# Tiny_Tetris_v1_3.net
KiCad netlist of a schematic drawn in EAGLE
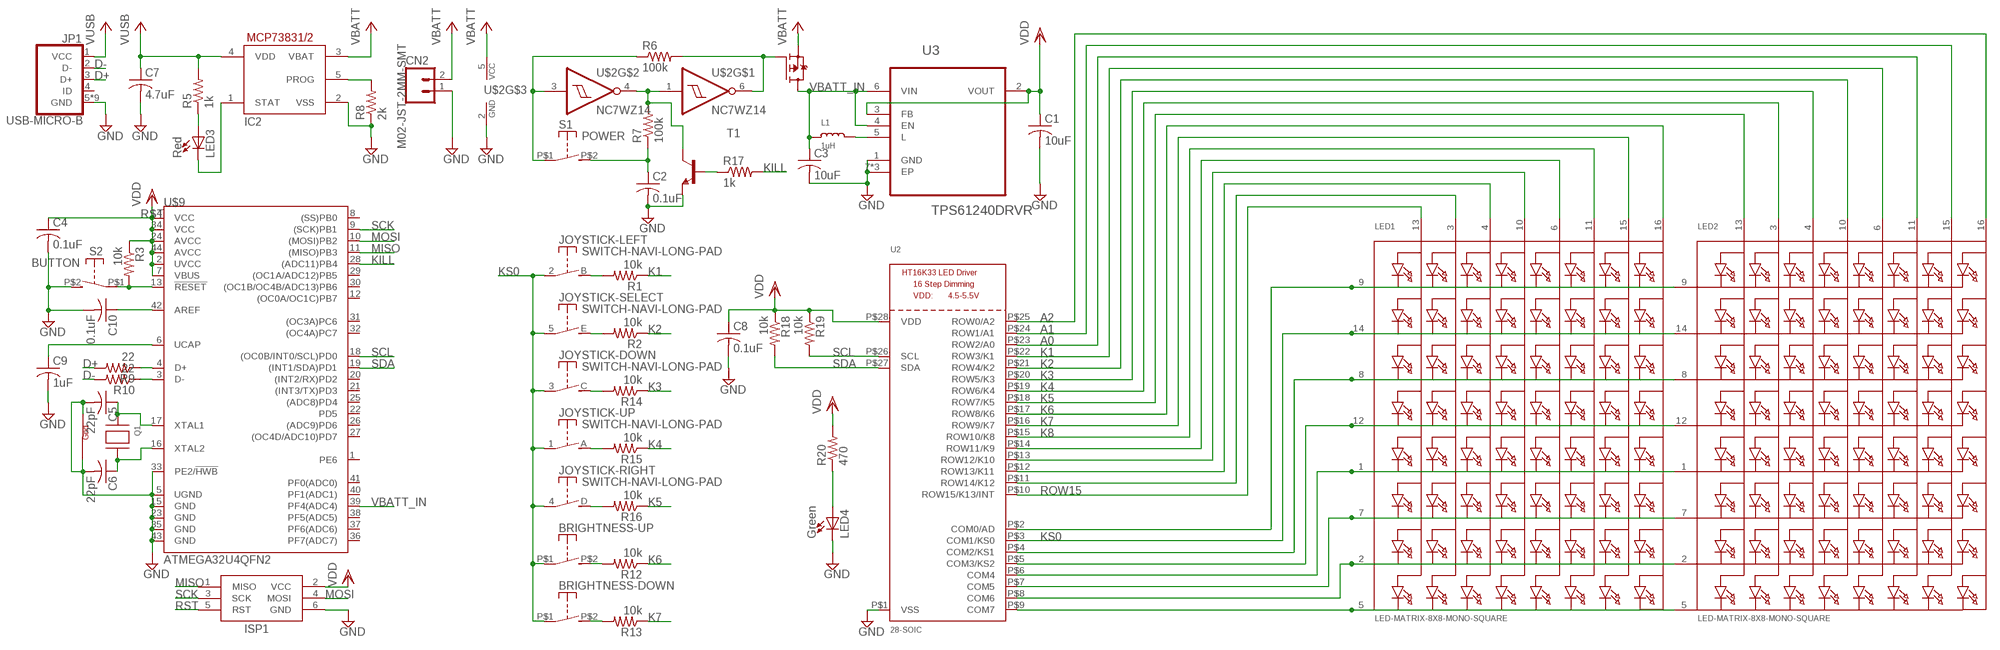
[diagram p0: schematic, sheet 1]

(export (version "E")
  (design (tool "Eeschema 10.0.6"))
  (components
    (comp (ref "BRIGHTNESS-DOWN")
      (value "SWITCH-TACTSKRELGE010")
      (footprint "eagle-import:TACT-ALPS-SKRELGE010")
      (libsource (lib "eagle-import") (part "SWITCH-TACTSKRELGE010"))
    )
    (comp (ref "BRIGHTNESS-UP")
      (value "SWITCH-TACTSKRELGE010")
      (footprint "eagle-import:TACT-ALPS-SKRELGE010")
      (libsource (lib "eagle-import") (part "SWITCH-TACTSKRELGE010"))
    )
    (comp (ref "C1")
      (value "10uF")
      (footprint "eagle-import:C0603K")
      (libsource (lib "eagle-import") (part "C-USC0603K"))
    )
    (comp (ref "C2")
      (value "0.1uF")
      (footprint "eagle-import:C0603K")
      (libsource (lib "eagle-import") (part "C-USC0603K"))
    )
    (comp (ref "C3")
      (value "10uF")
      (footprint "eagle-import:C0603K")
      (libsource (lib "eagle-import") (part "C-USC0603K"))
    )
    (comp (ref "C4")
      (value "0.1uF")
      (footprint "eagle-import:C0603K")
      (libsource (lib "eagle-import") (part "C-USC0603K"))
    )
    (comp (ref "C5")
      (value "22pF")
      (footprint "eagle-import:C0603K")
      (libsource (lib "eagle-import") (part "C-USC0603K"))
    )
    (comp (ref "C6")
      (value "22pF")
      (footprint "eagle-import:C0603K")
      (libsource (lib "eagle-import") (part "C-USC0603K"))
    )
    (comp (ref "C7")
      (value "4.7uF")
      (footprint "eagle-import:C0603K")
      (libsource (lib "eagle-import") (part "C-USC0603K"))
    )
    (comp (ref "C8")
      (value "0.1uF")
      (footprint "eagle-import:C0603K")
      (libsource (lib "eagle-import") (part "C-USC0603K"))
    )
    (comp (ref "C9")
      (value "1uF")
      (footprint "eagle-import:C0603K")
      (libsource (lib "eagle-import") (part "C-USC0603K"))
    )
    (comp (ref "C10")
      (value "0.1uF")
      (footprint "eagle-import:C0603K")
      (libsource (lib "eagle-import") (part "C-USC0603K"))
    )
    (comp (ref "CN2")
      (value "M02-JST-2MM-SMT")
      (footprint "eagle-import:1X02_NO_SILK")
      (libsource (lib "eagle-import") (part "M021X02_NO_SILK"))
    )
    (comp (ref "IC2")
      (value "MCP73831/OT")
      (footprint "eagle-import:SOT23-5L")
      (libsource (lib "eagle-import") (part "MCP73831/OT"))
    )
    (comp (ref "ISP1")
      (value "AVRISP-6")
      (footprint "eagle-import:AVRISP")
      (libsource (lib "eagle-import") (part "AVRISP-6"))
    )
    (comp (ref "JOYSTICK-")
      (value "SWITCH-NAVI-LONG-PAD")
      (footprint "eagle-import:JOYSTICK-NOKIA-3230-LONG-PAD")
      (libsource (lib "eagle-import") (part "SWITCH-NAVI-LONG-PAD"))
    )
    (comp (ref "JP1")
      (value "USB-MICRO-B")
      (footprint "eagle-import:MICRO-USB-FCI-10103594")
      (libsource (lib "eagle-import") (part "USB-MICRO-B"))
    )
    (comp (ref "L1")
      (value "1uH")
      (footprint "eagle-import:0805")
      (libsource (lib "eagle-import") (part "INDUCTOR0805"))
    )
    (comp (ref "LED1")
      (value "LED-MATRIX-8X8-MONO-SQUARE")
      (footprint "eagle-import:LED-MATRIX-8X8-MONO-SQUARE")
      (libsource (lib "eagle-import") (part "LED-MATRIX-8X8-MONO-SQUARE"))
    )
    (comp (ref "LED2")
      (value "LED-MATRIX-8X8-MONO-SQUARE")
      (footprint "eagle-import:LED-MATRIX-8X8-MONO-SQUARE")
      (libsource (lib "eagle-import") (part "LED-MATRIX-8X8-MONO-SQUARE"))
    )
    (comp (ref "LED3")
      (value "Red")
      (footprint "eagle-import:LED-0603-SIDEVIEW")
      (libsource (lib "eagle-import") (part "LED"))
    )
    (comp (ref "LED4")
      (value "Green")
      (footprint "eagle-import:LED-0603-SIDEVIEW")
      (libsource (lib "eagle-import") (part "LED"))
    )
    (comp (ref "Q1")
      (value "XTAL-4-3225")
      (footprint "eagle-import:NX3225")
      (libsource (lib "eagle-import") (part "XTAL-4-3225"))
    )
    (comp (ref "R1")
      (value "10k")
      (footprint "eagle-import:R0603")
      (libsource (lib "eagle-import") (part "R-US_R0603"))
    )
    (comp (ref "R2")
      (value "10k")
      (footprint "eagle-import:R0603")
      (libsource (lib "eagle-import") (part "R-US_R0603"))
    )
    (comp (ref "R3")
      (value "10k")
      (footprint "eagle-import:R0603")
      (libsource (lib "eagle-import") (part "R-US_R0603"))
    )
    (comp (ref "R5")
      (value "1k")
      (footprint "eagle-import:R0603")
      (libsource (lib "eagle-import") (part "R-US_R0603"))
    )
    (comp (ref "R6")
      (value "100k")
      (footprint "eagle-import:R0603")
      (libsource (lib "eagle-import") (part "R-US_R0603"))
    )
    (comp (ref "R7")
      (value "100k")
      (footprint "eagle-import:R0603")
      (libsource (lib "eagle-import") (part "R-US_R0603"))
    )
    (comp (ref "R8")
      (value "2k")
      (footprint "eagle-import:R0603")
      (libsource (lib "eagle-import") (part "R-US_R0603"))
    )
    (comp (ref "R9")
      (value "22")
      (footprint "eagle-import:R0603")
      (libsource (lib "eagle-import") (part "R-US_R0603"))
    )
    (comp (ref "R10")
      (value "22")
      (footprint "eagle-import:R0603")
      (libsource (lib "eagle-import") (part "R-US_R0603"))
    )
    (comp (ref "R12")
      (value "10k")
      (footprint "eagle-import:R0603")
      (libsource (lib "eagle-import") (part "R-US_R0603"))
    )
    (comp (ref "R13")
      (value "10k")
      (footprint "eagle-import:R0603")
      (libsource (lib "eagle-import") (part "R-US_R0603"))
    )
    (comp (ref "R14")
      (value "10k")
      (footprint "eagle-import:R0603")
      (libsource (lib "eagle-import") (part "R-US_R0603"))
    )
    (comp (ref "R15")
      (value "10k")
      (footprint "eagle-import:R0603")
      (libsource (lib "eagle-import") (part "R-US_R0603"))
    )
    (comp (ref "R16")
      (value "10k")
      (footprint "eagle-import:R0603")
      (libsource (lib "eagle-import") (part "R-US_R0603"))
    )
    (comp (ref "R17")
      (value "1k")
      (footprint "eagle-import:R0603")
      (libsource (lib "eagle-import") (part "R-US_R0603"))
    )
    (comp (ref "R18")
      (value "10k")
      (footprint "eagle-import:R0603")
      (libsource (lib "eagle-import") (part "R-US_R0603"))
    )
    (comp (ref "R19")
      (value "10k")
      (footprint "eagle-import:R0603")
      (libsource (lib "eagle-import") (part "R-US_R0603"))
    )
    (comp (ref "R20")
      (value "470")
      (footprint "eagle-import:R0603")
      (libsource (lib "eagle-import") (part "R-US_R0603"))
    )
    (comp (ref "S1")
      (value "POWER")
      (footprint "eagle-import:TACT-ALPS-SKRELGE010")
      (libsource (lib "eagle-import") (part "SWITCH-TACTSKRELGE010"))
    )
    (comp (ref "S2")
      (value "BUTTON")
      (footprint "eagle-import:TACT-ALPS-SKRELGE010")
      (libsource (lib "eagle-import") (part "SWITCH-TACTSKRELGE010"))
    )
    (comp (ref "T1")
      (value "MMBT2222ALT1-NPN-SOT23-BEC")
      (footprint "eagle-import:SOT23-BEC")
      (libsource (lib "eagle-import") (part "-NPN-SOT23-BECMMBT2222ALT1"))
    )
    (comp (ref "U$1")
      (value "IRLML6402")
      (footprint "eagle-import:SOT23")
      (libsource (lib "eagle-import") (part "IRLML6402"))
    )
    (comp (ref "U$2")
      (value "NC7WZ14")
      (footprint "eagle-import:SC-70-6")
      (libsource (lib "eagle-import") (part "NC7WZ14"))
    )
    (comp (ref "U$9")
      (value "ATMEGA32U4QFN2")
      (footprint "eagle-import:SPARKFUN-DIGITALIC_QFN-44-NOPAD")
      (libsource (lib "eagle-import") (part "ATMEGA32U4QFN2"))
    )
    (comp (ref "U2")
      (value "28-SOIC")
      (footprint "eagle-import:SOP28_300MIL")
      (libsource (lib "eagle-import") (part "HT16K33_SOP28"))
    )
    (comp (ref "U3")
      (value "TPS61240DRVR")
      (footprint "eagle-import:SON65P200X200X80-7N")
      (libsource (lib "eagle-import") (part "TPS61240DRVR"))
    )
  )
  (nets
    (net (code "1") (name "/A0") (class "Default")
      (node (ref "LED2") (pin "11") (pinfunction "A6_11") (pintype "bidirectional"))
      (node (ref "U2") (pin "P$23") (pinfunction "ROW2/A0_P$23") (pintype "bidirectional"))
    )
    (net (code "2") (name "/A1") (class "Default")
      (node (ref "LED2") (pin "15") (pinfunction "A7_15") (pintype "bidirectional"))
      (node (ref "U2") (pin "P$24") (pinfunction "ROW1/A1_P$24") (pintype "bidirectional"))
    )
    (net (code "3") (name "/A2") (class "Default")
      (node (ref "LED2") (pin "16") (pinfunction "A8_16") (pintype "bidirectional"))
      (node (ref "U2") (pin "P$25") (pinfunction "ROW0/A2_P$25") (pintype "bidirectional"))
    )
    (net (code "4") (name "/D+") (class "Default")
      (node (ref "JP1") (pin "3") (pinfunction "D+_3") (pintype "bidirectional"))
      (node (ref "R9") (pin "2") (pinfunction "2_2") (pintype "passive"))
    )
    (net (code "5") (name "/D-") (class "Default")
      (node (ref "JP1") (pin "2") (pinfunction "D-_2") (pintype "bidirectional"))
      (node (ref "R10") (pin "2") (pinfunction "2_2") (pintype "passive"))
    )
    (net (code "6") (name "/K1") (class "Default")
      (node (ref "LED2") (pin "6") (pinfunction "A5_6") (pintype "bidirectional"))
      (node (ref "R1") (pin "1") (pinfunction "1_1") (pintype "passive"))
      (node (ref "U2") (pin "P$22") (pinfunction "ROW3/K1_P$22") (pintype "bidirectional"))
    )
    (net (code "7") (name "/K2") (class "Default")
      (node (ref "LED2") (pin "10") (pinfunction "A4_10") (pintype "bidirectional"))
      (node (ref "R2") (pin "1") (pinfunction "1_1") (pintype "passive"))
      (node (ref "U2") (pin "P$21") (pinfunction "ROW4/K2_P$21") (pintype "bidirectional"))
    )
    (net (code "8") (name "/K3") (class "Default")
      (node (ref "LED2") (pin "4") (pinfunction "A3_4") (pintype "bidirectional"))
      (node (ref "R14") (pin "1") (pinfunction "1_1") (pintype "passive"))
      (node (ref "U2") (pin "P$20") (pinfunction "ROW5/K3_P$20") (pintype "bidirectional"))
    )
    (net (code "9") (name "/K4") (class "Default")
      (node (ref "LED2") (pin "3") (pinfunction "A2_3") (pintype "bidirectional"))
      (node (ref "R15") (pin "1") (pinfunction "1_1") (pintype "passive"))
      (node (ref "U2") (pin "P$19") (pinfunction "ROW6/K4_P$19") (pintype "bidirectional"))
    )
    (net (code "10") (name "/K5") (class "Default")
      (node (ref "LED2") (pin "13") (pinfunction "A1_13") (pintype "bidirectional"))
      (node (ref "R16") (pin "1") (pinfunction "1_1") (pintype "passive"))
      (node (ref "U2") (pin "P$18") (pinfunction "ROW7/K5_P$18") (pintype "bidirectional"))
    )
    (net (code "11") (name "/K6") (class "Default")
      (node (ref "LED1") (pin "16") (pinfunction "A8_16") (pintype "bidirectional"))
      (node (ref "R12") (pin "1") (pinfunction "1_1") (pintype "passive"))
      (node (ref "U2") (pin "P$17") (pinfunction "ROW8/K6_P$17") (pintype "bidirectional"))
    )
    (net (code "12") (name "/K7") (class "Default")
      (node (ref "LED1") (pin "15") (pinfunction "A7_15") (pintype "bidirectional"))
      (node (ref "R13") (pin "1") (pinfunction "1_1") (pintype "passive"))
      (node (ref "U2") (pin "P$16") (pinfunction "ROW9/K7_P$16") (pintype "bidirectional"))
    )
    (net (code "13") (name "/K8") (class "Default")
      (node (ref "LED1") (pin "11") (pinfunction "A6_11") (pintype "bidirectional"))
      (node (ref "U2") (pin "P$15") (pinfunction "ROW10/K8_P$15") (pintype "bidirectional"))
    )
    (net (code "14") (name "/KILL") (class "Default")
      (node (ref "R17") (pin "2") (pinfunction "2_2") (pintype "passive"))
      (node (ref "U$9") (pin "28") (pinfunction "(ADC11)PB4_28") (pintype "bidirectional"))
    )
    (net (code "15") (name "/KS0") (class "Default")
      (node (ref "BRIGHTNESS-DOWN") (pin "P$1") (pinfunction "P_P$1") (pintype "passive"))
      (node (ref "BRIGHTNESS-UP") (pin "P$1") (pinfunction "P_P$1") (pintype "passive"))
      (node (ref "JOYSTICK-") (pin "1") (pinfunction "P_1") (pintype "passive"))
      (node (ref "JOYSTICK-") (pin "2") (pinfunction "P_2") (pintype "passive"))
      (node (ref "JOYSTICK-") (pin "3") (pinfunction "P_3") (pintype "passive"))
      (node (ref "JOYSTICK-") (pin "4") (pinfunction "P_4") (pintype "passive"))
      (node (ref "JOYSTICK-") (pin "5") (pinfunction "P_5") (pintype "passive"))
      (node (ref "LED1") (pin "14") (pinfunction "K2_14") (pintype "bidirectional"))
      (node (ref "LED2") (pin "14") (pinfunction "K2_14") (pintype "bidirectional"))
      (node (ref "U2") (pin "P$3") (pinfunction "COM1/KS0_P$3") (pintype "bidirectional"))
    )
    (net (code "16") (name "/MISO") (class "Default")
      (node (ref "ISP1") (pin "1") (pinfunction "MISO_1") (pintype "input"))
      (node (ref "U$9") (pin "11") (pinfunction "(MISO)PB3_11") (pintype "bidirectional"))
    )
    (net (code "17") (name "/MOSI") (class "Default")
      (node (ref "ISP1") (pin "4") (pinfunction "MOSI_4") (pintype "output"))
      (node (ref "U$9") (pin "10") (pinfunction "(MOSI)PB2_10") (pintype "bidirectional"))
    )
    (net (code "18") (name "/ROW15") (class "Default")
      (node (ref "LED1") (pin "13") (pinfunction "A1_13") (pintype "bidirectional"))
      (node (ref "U2") (pin "P$10") (pinfunction "ROW15/K13/INT_P$10") (pintype "bidirectional"))
    )
    (net (code "19") (name "/RST") (class "Default")
      (node (ref "ISP1") (pin "5") (pinfunction "RST_5") (pintype "output"))
      (node (ref "R3") (pin "2") (pinfunction "2_2") (pintype "passive"))
      (node (ref "S2") (pin "P$1") (pinfunction "P_P$1") (pintype "passive"))
      (node (ref "U$9") (pin "13") (pinfunction "~{RESET}_13") (pintype "bidirectional"))
    )
    (net (code "20") (name "/SCK") (class "Default")
      (node (ref "ISP1") (pin "3") (pinfunction "SCK_3") (pintype "output"))
      (node (ref "U$9") (pin "9") (pinfunction "(SCK)PB1_9") (pintype "bidirectional"))
    )
    (net (code "21") (name "/SCL") (class "Default")
      (node (ref "R19") (pin "2") (pinfunction "2_2") (pintype "passive"))
      (node (ref "U$9") (pin "18") (pinfunction "(OC0B/INT0/SCL)PD0_18") (pintype "bidirectional"))
      (node (ref "U2") (pin "P$26") (pinfunction "SCL_P$26") (pintype "bidirectional"))
    )
    (net (code "22") (name "/SDA") (class "Default")
      (node (ref "R18") (pin "2") (pinfunction "2_2") (pintype "passive"))
      (node (ref "U$9") (pin "19") (pinfunction "(INT1/SDA)PD1_19") (pintype "bidirectional"))
      (node (ref "U2") (pin "P$27") (pinfunction "SDA_P$27") (pintype "bidirectional"))
    )
    (net (code "23") (name "/VBATT_IN") (class "Default")
      (node (ref "C3") (pin "1") (pinfunction "1_1") (pintype "passive"))
      (node (ref "L1") (pin "1") (pinfunction "1_1") (pintype "passive"))
      (node (ref "U$1") (pin "3") (pinfunction "D_3") (pintype "passive"))
      (node (ref "U$9") (pin "39") (pinfunction "PF4(ADC4)_39") (pintype "bidirectional"))
      (node (ref "U3") (pin "4") (pinfunction "EN_4") (pintype "input"))
      (node (ref "U3") (pin "6") (pinfunction "VIN_6") (pintype "power_in"))
    )
    (net (code "24") (name "GND") (class "Default")
      (node (ref "C1") (pin "2") (pinfunction "2_2") (pintype "passive"))
      (node (ref "C10") (pin "2") (pinfunction "2_2") (pintype "passive"))
      (node (ref "C2") (pin "2") (pinfunction "2_2") (pintype "passive"))
      (node (ref "C3") (pin "2") (pinfunction "2_2") (pintype "passive"))
      (node (ref "C4") (pin "2") (pinfunction "2_2") (pintype "passive"))
      (node (ref "C5") (pin "2") (pinfunction "2_2") (pintype "passive"))
      (node (ref "C6") (pin "2") (pinfunction "2_2") (pintype "passive"))
      (node (ref "C7") (pin "2") (pinfunction "2_2") (pintype "passive"))
      (node (ref "C8") (pin "2") (pinfunction "2_2") (pintype "passive"))
      (node (ref "C9") (pin "2") (pinfunction "2_2") (pintype "passive"))
      (node (ref "CN2") (pin "1") (pinfunction "1_1") (pintype "passive"))
      (node (ref "IC2") (pin "2") (pinfunction "VSS_2") (pintype "power_in"))
      (node (ref "ISP1") (pin "6") (pinfunction "GND_6") (pintype "power_in"))
      (node (ref "JP1") (pin "5") (pinfunction "GND_5") (pintype "bidirectional"))
      (node (ref "JP1") (pin "P$1") (pinfunction "GND_P$1") (pintype "bidirectional"))
      (node (ref "JP1") (pin "P$2") (pinfunction "GND_P$2") (pintype "bidirectional"))
      (node (ref "JP1") (pin "P$3") (pinfunction "GND_P$3") (pintype "bidirectional"))
      (node (ref "JP1") (pin "P$4") (pinfunction "GND_P$4") (pintype "bidirectional"))
      (node (ref "JP1") (pin "P$5") (pinfunction "GND_P$5") (pintype "bidirectional"))
      (node (ref "JP1") (pin "P$6") (pinfunction "GND_P$6") (pintype "bidirectional"))
      (node (ref "JP1") (pin "P$7") (pinfunction "GND_P$7") (pintype "bidirectional"))
      (node (ref "JP1") (pin "P$8") (pinfunction "GND_P$8") (pintype "bidirectional"))
      (node (ref "LED4") (pin "P$2") (pinfunction "C_P$2") (pintype "passive"))
      (node (ref "Q1") (pin "2") (pinfunction "G2_2") (pintype "power_in"))
      (node (ref "Q1") (pin "4") (pinfunction "G1_4") (pintype "power_in"))
      (node (ref "R8") (pin "1") (pinfunction "1_1") (pintype "passive"))
      (node (ref "S2") (pin "P$2") (pinfunction "S_P$2") (pintype "passive"))
      (node (ref "T1") (pin "E") (pinfunction "E_E") (pintype "passive"))
      (node (ref "U$2") (pin "2") (pinfunction "GND_2") (pintype "power_in"))
      (node (ref "U$9") (pin "15") (pinfunction "GND_15") (pintype "bidirectional"))
      (node (ref "U$9") (pin "23") (pinfunction "GND_23") (pintype "bidirectional"))
      (node (ref "U$9") (pin "33") (pinfunction "PE2/~{HWB}_33") (pintype "bidirectional"))
      (node (ref "U$9") (pin "35") (pinfunction "GND_35") (pintype "bidirectional"))
      (node (ref "U$9") (pin "43") (pinfunction "GND_43") (pintype "bidirectional"))
      (node (ref "U$9") (pin "5") (pinfunction "UGND_5") (pintype "bidirectional"))
      (node (ref "U2") (pin "P$1") (pinfunction "VSS_P$1") (pintype "bidirectional"))
      (node (ref "U3") (pin "1") (pinfunction "GND_1") (pintype "passive"))
      (node (ref "U3") (pin "7") (pinfunction "EP_7") (pintype "passive"))
      (node (ref "U3") (pin "8") (pinfunction "EP_8") (pintype "passive"))
      (node (ref "U3") (pin "9") (pinfunction "EP_9") (pintype "passive"))
    )
    (net (code "25") (name "Net-(BRIGHTNESS-DOWN-S)") (class "Default")
      (node (ref "BRIGHTNESS-DOWN") (pin "P$2") (pinfunction "S_P$2") (pintype "passive"))
      (node (ref "R13") (pin "2") (pinfunction "2_2") (pintype "passive"))
    )
    (net (code "26") (name "Net-(BRIGHTNESS-UP-S)") (class "Default")
      (node (ref "BRIGHTNESS-UP") (pin "P$2") (pinfunction "S_P$2") (pintype "passive"))
      (node (ref "R12") (pin "2") (pinfunction "2_2") (pintype "passive"))
    )
    (net (code "27") (name "Net-(IC2-PROG)") (class "Default")
      (node (ref "IC2") (pin "5") (pinfunction "PROG_5") (pintype "input"))
      (node (ref "R8") (pin "2") (pinfunction "2_2") (pintype "passive"))
    )
    (net (code "28") (name "Net-(IC2-STAT)") (class "Default")
      (node (ref "IC2") (pin "1") (pinfunction "STAT_1") (pintype "output"))
      (node (ref "LED3") (pin "P$2") (pinfunction "C_P$2") (pintype "passive"))
    )
    (net (code "29") (name "Net-(JOYSTICK-A-S)") (class "Default")
      (node (ref "JOYSTICK-") (pin "C") (pinfunction "S_C") (pintype "passive"))
      (node (ref "R14") (pin "2") (pinfunction "2_2") (pintype "passive"))
    )
    (net (code "30") (name "Net-(JOYSTICK-B-S)") (class "Default")
      (node (ref "JOYSTICK-") (pin "B") (pinfunction "S_B") (pintype "passive"))
      (node (ref "R1") (pin "2") (pinfunction "2_2") (pintype "passive"))
    )
    (net (code "31") (name "Net-(JOYSTICK-C-S)") (class "Default")
      (node (ref "JOYSTICK-") (pin "D") (pinfunction "S_D") (pintype "passive"))
      (node (ref "R16") (pin "2") (pinfunction "2_2") (pintype "passive"))
    )
    (net (code "32") (name "Net-(JOYSTICK-D-S)") (class "Default")
      (node (ref "JOYSTICK-") (pin "E") (pinfunction "S_E") (pintype "passive"))
      (node (ref "R2") (pin "2") (pinfunction "2_2") (pintype "passive"))
    )
    (net (code "33") (name "Net-(JOYSTICK-E-S)") (class "Default")
      (node (ref "JOYSTICK-") (pin "A") (pinfunction "S_A") (pintype "passive"))
      (node (ref "R15") (pin "2") (pinfunction "2_2") (pintype "passive"))
    )
    (net (code "34") (name "Net-(LED1-A2)") (class "Default")
      (node (ref "LED1") (pin "3") (pinfunction "A2_3") (pintype "bidirectional"))
      (node (ref "U2") (pin "P$11") (pinfunction "ROW14/K12_P$11") (pintype "bidirectional"))
    )
    (net (code "35") (name "Net-(LED1-A3)") (class "Default")
      (node (ref "LED1") (pin "4") (pinfunction "A3_4") (pintype "bidirectional"))
      (node (ref "U2") (pin "P$12") (pinfunction "ROW13/K11_P$12") (pintype "bidirectional"))
    )
    (net (code "36") (name "Net-(LED1-A4)") (class "Default")
      (node (ref "LED1") (pin "10") (pinfunction "A4_10") (pintype "bidirectional"))
      (node (ref "U2") (pin "P$13") (pinfunction "ROW12/K10_P$13") (pintype "bidirectional"))
    )
    (net (code "37") (name "Net-(LED1-A5)") (class "Default")
      (node (ref "LED1") (pin "6") (pinfunction "A5_6") (pintype "bidirectional"))
      (node (ref "U2") (pin "P$14") (pinfunction "ROW11/K9_P$14") (pintype "bidirectional"))
    )
    (net (code "38") (name "Net-(LED1-K1)") (class "Default")
      (node (ref "LED1") (pin "9") (pinfunction "K1_9") (pintype "bidirectional"))
      (node (ref "LED2") (pin "9") (pinfunction "K1_9") (pintype "bidirectional"))
      (node (ref "U2") (pin "P$2") (pinfunction "COM0/AD_P$2") (pintype "bidirectional"))
    )
    (net (code "39") (name "Net-(LED1-K3)") (class "Default")
      (node (ref "LED1") (pin "8") (pinfunction "K3_8") (pintype "bidirectional"))
      (node (ref "LED2") (pin "8") (pinfunction "K3_8") (pintype "bidirectional"))
      (node (ref "U2") (pin "P$4") (pinfunction "COM2/KS1_P$4") (pintype "bidirectional"))
    )
    (net (code "40") (name "Net-(LED1-K4)") (class "Default")
      (node (ref "LED1") (pin "12") (pinfunction "K4_12") (pintype "bidirectional"))
      (node (ref "LED2") (pin "12") (pinfunction "K4_12") (pintype "bidirectional"))
      (node (ref "U2") (pin "P$5") (pinfunction "COM3/KS2_P$5") (pintype "bidirectional"))
    )
    (net (code "41") (name "Net-(LED1-K5)") (class "Default")
      (node (ref "LED1") (pin "1") (pinfunction "K5_1") (pintype "bidirectional"))
      (node (ref "LED2") (pin "1") (pinfunction "K5_1") (pintype "bidirectional"))
      (node (ref "U2") (pin "P$6") (pinfunction "COM4_P$6") (pintype "bidirectional"))
    )
    (net (code "42") (name "Net-(LED1-K6)") (class "Default")
      (node (ref "LED1") (pin "7") (pinfunction "K6_7") (pintype "bidirectional"))
      (node (ref "LED2") (pin "7") (pinfunction "K6_7") (pintype "bidirectional"))
      (node (ref "U2") (pin "P$7") (pinfunction "COM5_P$7") (pintype "bidirectional"))
    )
    (net (code "43") (name "Net-(LED1-K7)") (class "Default")
      (node (ref "LED1") (pin "2") (pinfunction "K7_2") (pintype "bidirectional"))
      (node (ref "LED2") (pin "2") (pinfunction "K7_2") (pintype "bidirectional"))
      (node (ref "U2") (pin "P$8") (pinfunction "COM6_P$8") (pintype "bidirectional"))
    )
    (net (code "44") (name "Net-(LED1-K8)") (class "Default")
      (node (ref "LED1") (pin "5") (pinfunction "K8_5") (pintype "bidirectional"))
      (node (ref "LED2") (pin "5") (pinfunction "K8_5") (pintype "bidirectional"))
      (node (ref "U2") (pin "P$9") (pinfunction "COM7_P$9") (pintype "bidirectional"))
    )
    (net (code "45") (name "Net-(LED3-A)") (class "Default")
      (node (ref "LED3") (pin "P$1") (pinfunction "A_P$1") (pintype "passive"))
      (node (ref "R5") (pin "1") (pinfunction "1_1") (pintype "passive"))
    )
    (net (code "46") (name "Net-(LED4-A)") (class "Default")
      (node (ref "LED4") (pin "P$1") (pinfunction "A_P$1") (pintype "passive"))
      (node (ref "R20") (pin "1") (pinfunction "1_1") (pintype "passive"))
    )
    (net (code "47") (name "Net-(Q1-X1)") (class "Default")
      (node (ref "C5") (pin "1") (pinfunction "1_1") (pintype "passive"))
      (node (ref "Q1") (pin "1") (pinfunction "X1_1") (pintype "bidirectional"))
      (node (ref "U$9") (pin "17") (pinfunction "XTAL1_17") (pintype "bidirectional"))
    )
    (net (code "48") (name "Net-(Q1-X2)") (class "Default")
      (node (ref "C6") (pin "1") (pinfunction "1_1") (pintype "passive"))
      (node (ref "Q1") (pin "3") (pinfunction "X2_3") (pintype "bidirectional"))
      (node (ref "U$9") (pin "16") (pinfunction "XTAL2_16") (pintype "bidirectional"))
    )
    (net (code "49") (name "Net-(R17-Pad1)") (class "Default")
      (node (ref "R17") (pin "1") (pinfunction "1_1") (pintype "passive"))
      (node (ref "T1") (pin "B") (pinfunction "B_B") (pintype "passive"))
    )
    (net (code "50") (name "Net-(S1-P)") (class "Default")
      (node (ref "R6") (pin "1") (pinfunction "1_1") (pintype "passive"))
      (node (ref "S1") (pin "P$1") (pinfunction "P_P$1") (pintype "passive"))
      (node (ref "U$2") (pin "3") (pinfunction "I_3") (pintype "input"))
    )
    (net (code "51") (name "Net-(S1-S)") (class "Default")
      (node (ref "C2") (pin "1") (pinfunction "1_1") (pintype "passive"))
      (node (ref "R7") (pin "1") (pinfunction "1_1") (pintype "passive"))
      (node (ref "S1") (pin "P$2") (pinfunction "S_P$2") (pintype "passive"))
    )
    (net (code "52") (name "Net-(U$1-G)") (class "Default")
      (node (ref "R6") (pin "2") (pinfunction "2_2") (pintype "passive"))
      (node (ref "U$1") (pin "1") (pinfunction "G_1") (pintype "passive"))
      (node (ref "U$2") (pin "6") (pinfunction "O_6") (pintype "output"))
    )
    (net (code "53") (name "Net-(U$2A-I)") (class "Default")
      (node (ref "R7") (pin "2") (pinfunction "2_2") (pintype "passive"))
      (node (ref "T1") (pin "C") (pinfunction "C_C") (pintype "passive"))
      (node (ref "U$2") (pin "1") (pinfunction "I_1") (pintype "input"))
      (node (ref "U$2") (pin "4") (pinfunction "O_4") (pintype "output"))
    )
    (net (code "54") (name "Net-(U$9-AREF)") (class "Default")
      (node (ref "C10") (pin "1") (pinfunction "1_1") (pintype "passive"))
      (node (ref "U$9") (pin "42") (pinfunction "AREF_42") (pintype "bidirectional"))
    )
    (net (code "55") (name "Net-(U$9-D+)") (class "Default")
      (node (ref "R9") (pin "1") (pinfunction "1_1") (pintype "passive"))
      (node (ref "U$9") (pin "4") (pinfunction "D+_4") (pintype "bidirectional"))
    )
    (net (code "56") (name "Net-(U$9-D-)") (class "Default")
      (node (ref "R10") (pin "1") (pinfunction "1_1") (pintype "passive"))
      (node (ref "U$9") (pin "3") (pinfunction "D-_3") (pintype "bidirectional"))
    )
    (net (code "57") (name "Net-(U$9-UCAP)") (class "Default")
      (node (ref "C9") (pin "1") (pinfunction "1_1") (pintype "passive"))
      (node (ref "U$9") (pin "6") (pinfunction "UCAP_6") (pintype "bidirectional"))
    )
    (net (code "58") (name "Net-(U3-L)") (class "Default")
      (node (ref "L1") (pin "2") (pinfunction "2_2") (pintype "passive"))
      (node (ref "U3") (pin "5") (pinfunction "L_5") (pintype "input"))
    )
    (net (code "59") (name "VBATT") (class "Default")
      (node (ref "CN2") (pin "2") (pinfunction "2_2") (pintype "passive"))
      (node (ref "IC2") (pin "3") (pinfunction "VBAT_3") (pintype "bidirectional"))
      (node (ref "U$1") (pin "2") (pinfunction "S_2") (pintype "passive"))
      (node (ref "U$2") (pin "5") (pinfunction "VCC_5") (pintype "power_in"))
    )
    (net (code "60") (name "VDD") (class "Default")
      (node (ref "C1") (pin "1") (pinfunction "1_1") (pintype "passive"))
      (node (ref "C4") (pin "1") (pinfunction "1_1") (pintype "passive"))
      (node (ref "C8") (pin "1") (pinfunction "1_1") (pintype "passive"))
      (node (ref "ISP1") (pin "2") (pinfunction "VCC_2") (pintype "power_in"))
      (node (ref "R18") (pin "1") (pinfunction "1_1") (pintype "passive"))
      (node (ref "R19") (pin "1") (pinfunction "1_1") (pintype "passive"))
      (node (ref "R20") (pin "2") (pinfunction "2_2") (pintype "passive"))
      (node (ref "R3") (pin "1") (pinfunction "1_1") (pintype "passive"))
      (node (ref "U$9") (pin "14") (pinfunction "VCC_14") (pintype "bidirectional"))
      (node (ref "U$9") (pin "2") (pinfunction "UVCC_2") (pintype "bidirectional"))
      (node (ref "U$9") (pin "24") (pinfunction "AVCC_24") (pintype "bidirectional"))
      (node (ref "U$9") (pin "34") (pinfunction "VCC_34") (pintype "bidirectional"))
      (node (ref "U$9") (pin "44") (pinfunction "AVCC_44") (pintype "bidirectional"))
      (node (ref "U$9") (pin "7") (pinfunction "VBUS_7") (pintype "bidirectional"))
      (node (ref "U2") (pin "P$28") (pinfunction "VDD_P$28") (pintype "bidirectional"))
      (node (ref "U3") (pin "2") (pinfunction "VOUT_2") (pintype "power_in"))
      (node (ref "U3") (pin "3") (pinfunction "FB_3") (pintype "input"))
    )
    (net (code "61") (name "VUSB") (class "Default")
      (node (ref "C7") (pin "1") (pinfunction "1_1") (pintype "passive"))
      (node (ref "IC2") (pin "4") (pinfunction "VDD_4") (pintype "power_in"))
      (node (ref "JP1") (pin "1") (pinfunction "VCC_1") (pintype "bidirectional"))
      (node (ref "R5") (pin "2") (pinfunction "2_2") (pintype "passive"))
    )
    (net (code "62") (name "unconnected-(JP1-ID-Pad4)") (class "Default")
      (node (ref "JP1") (pin "4") (pinfunction "ID_4") (pintype "bidirectional"))
    )
    (net (code "63") (name "unconnected-(U$9-(ADC8)PD4-Pad25)") (class "Default")
      (node (ref "U$9") (pin "25") (pinfunction "(ADC8)PD4_25") (pintype "bidirectional"))
    )
    (net (code "64") (name "unconnected-(U$9-(ADC9)PD6-Pad26)") (class "Default")
      (node (ref "U$9") (pin "26") (pinfunction "(ADC9)PD6_26") (pintype "bidirectional"))
    )
    (net (code "65") (name "unconnected-(U$9-(INT2{slash}RX)PD2-Pad20)") (class "Default")
      (node (ref "U$9") (pin "20") (pinfunction "(INT2/RX)PD2_20") (pintype "bidirectional"))
    )
    (net (code "66") (name "unconnected-(U$9-(INT3{slash}TX)PD3-Pad21)") (class "Default")
      (node (ref "U$9") (pin "21") (pinfunction "(INT3/TX)PD3_21") (pintype "bidirectional"))
    )
    (net (code "67") (name "unconnected-(U$9-(OC0A{slash}OC1C)PB7-Pad12)") (class "Default")
      (node (ref "U$9") (pin "12") (pinfunction "(OC0A/OC1C)PB7_12") (pintype "bidirectional"))
    )
    (net (code "68") (name "unconnected-(U$9-(OC1A{slash}ADC12)PB5-Pad29)") (class "Default")
      (node (ref "U$9") (pin "29") (pinfunction "(OC1A/ADC12)PB5_29") (pintype "bidirectional"))
    )
    (net (code "69") (name "unconnected-(U$9-(OC1B{slash}OC4B{slash}ADC13)PB6-Pad30)") (class "Default")
      (node (ref "U$9") (pin "30") (pinfunction "(OC1B/OC4B/ADC13)PB6_30") (pintype "bidirectional"))
    )
    (net (code "70") (name "unconnected-(U$9-(OC3A)PC6-Pad31)") (class "Default")
      (node (ref "U$9") (pin "31") (pinfunction "(OC3A)PC6_31") (pintype "bidirectional"))
    )
    (net (code "71") (name "unconnected-(U$9-(OC4A)PC7-Pad32)") (class "Default")
      (node (ref "U$9") (pin "32") (pinfunction "(OC4A)PC7_32") (pintype "bidirectional"))
    )
    (net (code "72") (name "unconnected-(U$9-(OC4D{slash}ADC10)PD7-Pad27)") (class "Default")
      (node (ref "U$9") (pin "27") (pinfunction "(OC4D/ADC10)PD7_27") (pintype "bidirectional"))
    )
    (net (code "73") (name "unconnected-(U$9-(SS)PB0-Pad8)") (class "Default")
      (node (ref "U$9") (pin "8") (pinfunction "(SS)PB0_8") (pintype "bidirectional"))
    )
    (net (code "74") (name "unconnected-(U$9-PD5-Pad22)") (class "Default")
      (node (ref "U$9") (pin "22") (pinfunction "PD5_22") (pintype "bidirectional"))
    )
    (net (code "75") (name "unconnected-(U$9-PE6-Pad1)") (class "Default")
      (node (ref "U$9") (pin "1") (pinfunction "PE6_1") (pintype "bidirectional"))
    )
    (net (code "76") (name "unconnected-(U$9-PF0(ADC0)-Pad41)") (class "Default")
      (node (ref "U$9") (pin "41") (pinfunction "PF0(ADC0)_41") (pintype "bidirectional"))
    )
    (net (code "77") (name "unconnected-(U$9-PF1(ADC1)-Pad40)") (class "Default")
      (node (ref "U$9") (pin "40") (pinfunction "PF1(ADC1)_40") (pintype "bidirectional"))
    )
    (net (code "78") (name "unconnected-(U$9-PF5(ADC5)-Pad38)") (class "Default")
      (node (ref "U$9") (pin "38") (pinfunction "PF5(ADC5)_38") (pintype "bidirectional"))
    )
    (net (code "79") (name "unconnected-(U$9-PF6(ADC6)-Pad37)") (class "Default")
      (node (ref "U$9") (pin "37") (pinfunction "PF6(ADC6)_37") (pintype "bidirectional"))
    )
    (net (code "80") (name "unconnected-(U$9-PF7(ADC7)-Pad36)") (class "Default")
      (node (ref "U$9") (pin "36") (pinfunction "PF7(ADC7)_36") (pintype "bidirectional"))
    )
  )
)
